# 3V3.net
KiCad netlist of a schematic drawn in Altium Designer
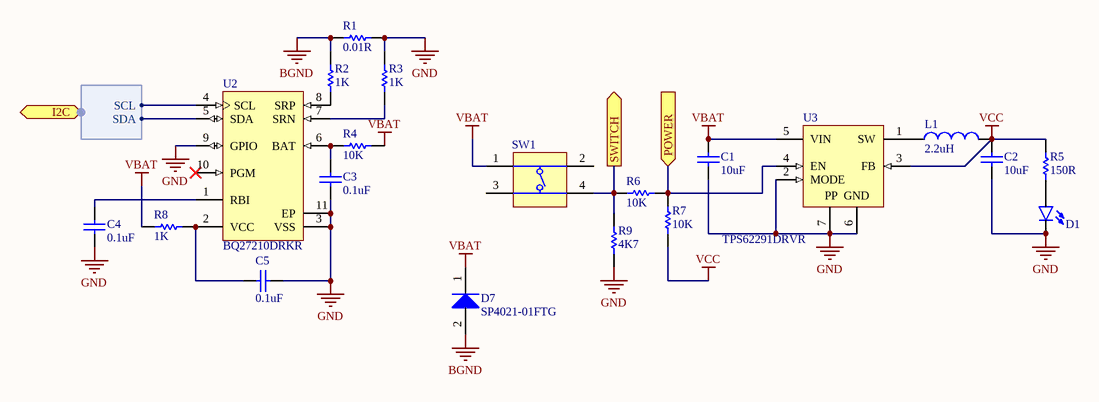
[diagram p0: 3V3.SchDoc]

(export (version "E")
  (design (tool "Eeschema 10.0.6"))
  (components
    (comp (ref "C1")
      (value "10uF")
      (footprint "C0402[1005X55]")
      (description "10uF 6.3V 20% 0402 (1005 Metric)")
      (fields (field (name "TOLERANCE") "20%") (field (name "PARTNUMBER") "GRM155R60J106ME44D"))
      (libsource (lib "Capacitors") (part "CAP_10uF_6.3V_0402_20%"))
    )
    (comp (ref "C2")
      (value "10uF")
      (footprint "C0402[1005X55]")
      (description "10uF 6.3V 20% 0402 (1005 Metric)")
      (fields (field (name "TOLERANCE") "20%") (field (name "PARTNUMBER") "GRM155R60J106ME44D"))
      (libsource (lib "Capacitors") (part "CAP_10uF_6.3V_0402_20%"))
    )
    (comp (ref "C3")
      (value "0.1uF")
      (footprint "C0402[1005X55]")
      (description "0.1uF 100V 10% 0402 (1005 Metric)")
      (fields (field (name "PARTNUMBER") "GRM155R62A104KE14D") (field (name "MANUFACTURER") "Murata"))
      (libsource (lib "Capacitors") (part "CAP_0.1uF_100V_0402_10%"))
    )
    (comp (ref "C4")
      (value "0.1uF")
      (footprint "C0402[1005X55]")
      (description "0.1uF 100V 10% 0402 (1005 Metric)")
      (fields (field (name "PARTNUMBER") "GRM155R62A104KE14D") (field (name "MANUFACTURER") "Murata"))
      (libsource (lib "Capacitors") (part "CAP_0.1uF_100V_0402_10%"))
    )
    (comp (ref "C5")
      (value "0.1uF")
      (footprint "C0402[1005X55]")
      (description "0.1uF 100V 10% 0402 (1005 Metric)")
      (fields (field (name "PARTNUMBER") "GRM155R62A104KE14D") (field (name "MANUFACTURER") "Murata"))
      (libsource (lib "Capacitors") (part "CAP_0.1uF_100V_0402_10%"))
    )
    (comp (ref "D1")
      (value "LED_0603_BLUE_5mA")
      (footprint "LED0603")
      (fields (field (name "PARTNUMBER") "LTST-C193TBKT-5A") (field (name "MANUFACTURER") "Lite-On Inc."))
      (libsource (lib "LEDs") (part "LED_0603_BLUE_5mA"))
    )
    (comp (ref "D7")
      (value "SP4021-01FTG")
      (footprint "SOD-323")
      (fields (field (name "MANUFACTURER") "Littelfuse"))
      (libsource (lib "Diodes") (part "SP4021-01FTG"))
    )
    (comp (ref "L1")
      (value "2.2uH")
      (footprint "IND0805")
      (description "2.2uH 20% 1.7A 0805")
      (fields (field (name "PARTNUMBER") "LQM21PN2R2MGHL") (field (name "MANUFACTURER") "Murata"))
      (libsource (lib "Inductors") (part "IND_2.2uH_1.7A_0805_20%"))
    )
    (comp (ref "R1")
      (value "0.01R")
      (footprint "R1206[3216]")
      (description "0.01R 1.5W 1% 1206 (3216 Metric)")
      (fields (field (name "MANUFACTURER") "KOA Speer") (field (name "PARTNUMBER") "TLR2BPDTD10L0F75"))
      (libsource (lib "Resistors") (part "RES_0.01R_1206_1%_1.5W"))
    )
    (comp (ref "R2")
      (value "1K")
      (footprint "R0402[1005]")
      (description "1K 0.063W 1% 0402 (1005 Metric)")
      (fields (field (name "MANUFACTURER") "KOA Speer") (field (name "PARTNUMBER") "RK73H1ETTP1001F"))
      (libsource (lib "Resistors") (part "RES_1K_0402_1%"))
    )
    (comp (ref "R3")
      (value "1K")
      (footprint "R0402[1005]")
      (description "1K 0.063W 1% 0402 (1005 Metric)")
      (fields (field (name "MANUFACTURER") "KOA Speer") (field (name "PARTNUMBER") "RK73H1ETTP1001F"))
      (libsource (lib "Resistors") (part "RES_1K_0402_1%"))
    )
    (comp (ref "R4")
      (value "10K")
      (footprint "R0402[1005]")
      (description "10K 0.063W 1% 0402 (1005 Metric)")
      (fields (field (name "MANUFACTURER") "KOA Speer") (field (name "PARTNUMBER") "RK73H1ETTP1002F"))
      (libsource (lib "Resistors") (part "RES_10K_0402_1%"))
    )
    (comp (ref "R5")
      (value "150R")
      (footprint "R0402[1005]")
      (description "150R 0.063W 1% 0402 (1005 Metric)")
      (fields (field (name "MANUFACTURER") "KOA Speer") (field (name "PARTNUMBER") "RK73H1ETTP1500F"))
      (libsource (lib "Resistors") (part "RES_150R_0402_1%"))
    )
    (comp (ref "R6")
      (value "10K")
      (footprint "R0402[1005]")
      (description "10K 0.063W 1% 0402 (1005 Metric)")
      (fields (field (name "MANUFACTURER") "KOA Speer") (field (name "PARTNUMBER") "RK73H1ETTP1002F"))
      (libsource (lib "Resistors") (part "RES_10K_0402_1%"))
    )
    (comp (ref "R7")
      (value "10K")
      (footprint "R0402[1005]")
      (description "10K 0.063W 1% 0402 (1005 Metric)")
      (fields (field (name "MANUFACTURER") "KOA Speer") (field (name "PARTNUMBER") "RK73H1ETTP1002F"))
      (libsource (lib "Resistors") (part "RES_10K_0402_1%"))
    )
    (comp (ref "R8")
      (value "1K")
      (footprint "R0402[1005]")
      (description "1K 0.063W 1% 0402 (1005 Metric)")
      (fields (field (name "MANUFACTURER") "KOA Speer") (field (name "PARTNUMBER") "RK73H1ETTP1001F"))
      (libsource (lib "Resistors") (part "RES_1K_0402_1%"))
    )
    (comp (ref "R9")
      (value "4K7")
      (footprint "R0402[1005]")
      (description "4K7 0.063W 1% 0402 (1005 Metric)")
      (fields (field (name "MANUFACTURER") "KOA Speer") (field (name "PARTNUMBER") "RK73H1ETTP4701F"))
      (libsource (lib "Resistors") (part "RES_4K7_0402_1%"))
    )
    (comp (ref "SW1")
      (value "~")
      (footprint "SWITCH")
      (description "Switch, SPNO Push Button SMD")
      (fields
        (field (name "MANUFACTURER") "C&K Components")
        (field (name "PARTNUMBER") "PTS810 SJM 250 SMTR LFS")
      )
      (libsource (lib "Components") (part "DIPT-DTSM-6"))
    )
    (comp (ref "U2")
      (value "BQ27210DRKR")
      (footprint "DRK0010A")
      (fields (field (name "MANUFACTURER") "Texas Instruments"))
      (libsource (lib "Altium Content Vault") (part "TI-BQ27210DRK10-2050X2650TP"))
    )
    (comp (ref "U3")
      (value "TPS62291DRVR")
      (footprint "WSON-6")
      (description "Voltage Regulators - Switching Regulators 2.25MHz 1A Step-Down Cnvrtr 3.3V Output")
      (fields (field (name "MANUFACTURER") "Texas Instruments"))
      (libsource (lib "ICs") (part "TPS62291DRVR"))
    )
  )
  (nets
    (net (code "2") (name "/POWER") (class "Default")
      (node (ref "R6") (pin "2") (pinfunction "2_2") (pintype "passive"))
      (node (ref "R7") (pin "2") (pinfunction "2_2") (pintype "passive"))
      (node (ref "U3") (pin "4") (pinfunction "EN_4") (pintype "input"))
    )
    (net (code "3") (name "/SCL") (class "Default")
      (node (ref "U2") (pin "4") (pinfunction "SCL_4") (pintype "input"))
    )
    (net (code "4") (name "/SDA") (class "Default")
      (node (ref "U2") (pin "5") (pinfunction "SDA_5") (pintype "bidirectional"))
    )
    (net (code "5") (name "/SWITCH") (class "Default")
      (node (ref "R6") (pin "1") (pinfunction "1_1") (pintype "passive"))
      (node (ref "R9") (pin "2") (pinfunction "2_2") (pintype "passive"))
      (node (ref "SW1") (pin "4") (pinfunction "T3_4") (pintype "passive"))
    )
    (net (code "7") (name "BGND") (class "Default")
      (node (ref "D7") (pin "2") (pinfunction "A_2") (pintype "passive"))
      (node (ref "R1") (pin "1") (pinfunction "1_1") (pintype "passive"))
      (node (ref "R2") (pin "2") (pinfunction "2_2") (pintype "passive"))
    )
    (net (code "8") (name "GND") (class "Default")
      (node (ref "C1") (pin "1") (pinfunction "1_1") (pintype "passive"))
      (node (ref "C2") (pin "1") (pinfunction "1_1") (pintype "passive"))
      (node (ref "C3") (pin "1") (pinfunction "1_1") (pintype "passive"))
      (node (ref "C4") (pin "1") (pinfunction "1_1") (pintype "passive"))
      (node (ref "C5") (pin "2") (pinfunction "2_2") (pintype "passive"))
      (node (ref "D1") (pin "C") (pinfunction "C_C") (pintype "passive"))
      (node (ref "R1") (pin "2") (pinfunction "2_2") (pintype "passive"))
      (node (ref "R3") (pin "2") (pinfunction "2_2") (pintype "passive"))
      (node (ref "R9") (pin "1") (pinfunction "1_1") (pintype "passive"))
      (node (ref "U2") (pin "11") (pinfunction "EP_11") (pintype "power_in"))
      (node (ref "U2") (pin "3") (pinfunction "VSS_3") (pintype "power_in"))
      (node (ref "U2") (pin "9") (pinfunction "GPIO_9") (pintype "bidirectional"))
      (node (ref "U3") (pin "2") (pinfunction "MODE_2") (pintype "input"))
      (node (ref "U3") (pin "6") (pinfunction "GND_6") (pintype "power_in"))
      (node (ref "U3") (pin "7") (pinfunction "EP_7") (pintype "passive"))
    )
    (net (code "9") (name "Net-(D1-PadA)") (class "Default")
      (node (ref "D1") (pin "A") (pinfunction "A_A") (pintype "passive"))
      (node (ref "R5") (pin "2") (pinfunction "2_2") (pintype "passive"))
    )
    (net (code "10") (name "Net-(U2-BAT)") (class "Default")
      (node (ref "C3") (pin "2") (pinfunction "2_2") (pintype "passive"))
      (node (ref "R4") (pin "1") (pinfunction "1_1") (pintype "passive"))
      (node (ref "U2") (pin "6") (pinfunction "BAT_6") (pintype "input"))
    )
    (net (code "11") (name "Net-(U2-RBI)") (class "Default")
      (node (ref "C4") (pin "2") (pinfunction "2_2") (pintype "passive"))
      (node (ref "U2") (pin "1") (pinfunction "RBI_1") (pintype "power_in"))
    )
    (net (code "12") (name "Net-(U2-SRN)") (class "Default")
      (node (ref "R3") (pin "1") (pinfunction "1_1") (pintype "passive"))
      (node (ref "U2") (pin "7") (pinfunction "SRN_7") (pintype "input"))
    )
    (net (code "13") (name "Net-(U2-SRP)") (class "Default")
      (node (ref "R2") (pin "1") (pinfunction "1_1") (pintype "passive"))
      (node (ref "U2") (pin "8") (pinfunction "SRP_8") (pintype "input"))
    )
    (net (code "14") (name "Net-(U2-VCC)") (class "Default")
      (node (ref "C5") (pin "1") (pinfunction "1_1") (pintype "passive"))
      (node (ref "R8") (pin "1") (pinfunction "1_1") (pintype "passive"))
      (node (ref "U2") (pin "2") (pinfunction "VCC_2") (pintype "power_in"))
    )
    (net (code "15") (name "Net-(U3-SW)") (class "Default")
      (node (ref "L1") (pin "1") (pinfunction "1_1") (pintype "passive"))
      (node (ref "U3") (pin "1") (pinfunction "SW_1") (pintype "power_in"))
    )
    (net (code "16") (name "VBAT") (class "Default")
      (node (ref "C1") (pin "2") (pinfunction "2_2") (pintype "passive"))
      (node (ref "D7") (pin "1") (pinfunction "K_1") (pintype "passive"))
      (node (ref "R4") (pin "2") (pinfunction "2_2") (pintype "passive"))
      (node (ref "R8") (pin "2") (pinfunction "2_2") (pintype "passive"))
      (node (ref "SW1") (pin "1") (pinfunction "T1_1") (pintype "passive"))
      (node (ref "U3") (pin "5") (pinfunction "VIN_5") (pintype "power_in"))
    )
    (net (code "17") (name "VCC") (class "Default")
      (node (ref "C2") (pin "2") (pinfunction "2_2") (pintype "passive"))
      (node (ref "L1") (pin "2") (pinfunction "2_2") (pintype "passive"))
      (node (ref "R5") (pin "1") (pinfunction "1_1") (pintype "passive"))
      (node (ref "R7") (pin "1") (pinfunction "1_1") (pintype "passive"))
      (node (ref "U3") (pin "3") (pinfunction "FB_3") (pintype "input"))
    )
    (net (code "18") (name "unconnected-(SW1-T2-Pad2)") (class "Default")
      (node (ref "SW1") (pin "2") (pinfunction "T2_2") (pintype "passive"))
    )
    (net (code "19") (name "unconnected-(SW1-T3-Pad3)") (class "Default")
      (node (ref "SW1") (pin "3") (pinfunction "T3_3") (pintype "passive"))
    )
    (net (code "20") (name "unconnected-(U2-PGM-Pad10)") (class "Default")
      (node (ref "U2") (pin "10") (pinfunction "PGM_10") (pintype "input+no_connect"))
    )
  )
)
